# Power.net
KiCad netlist of a schematic drawn in Altium Designer
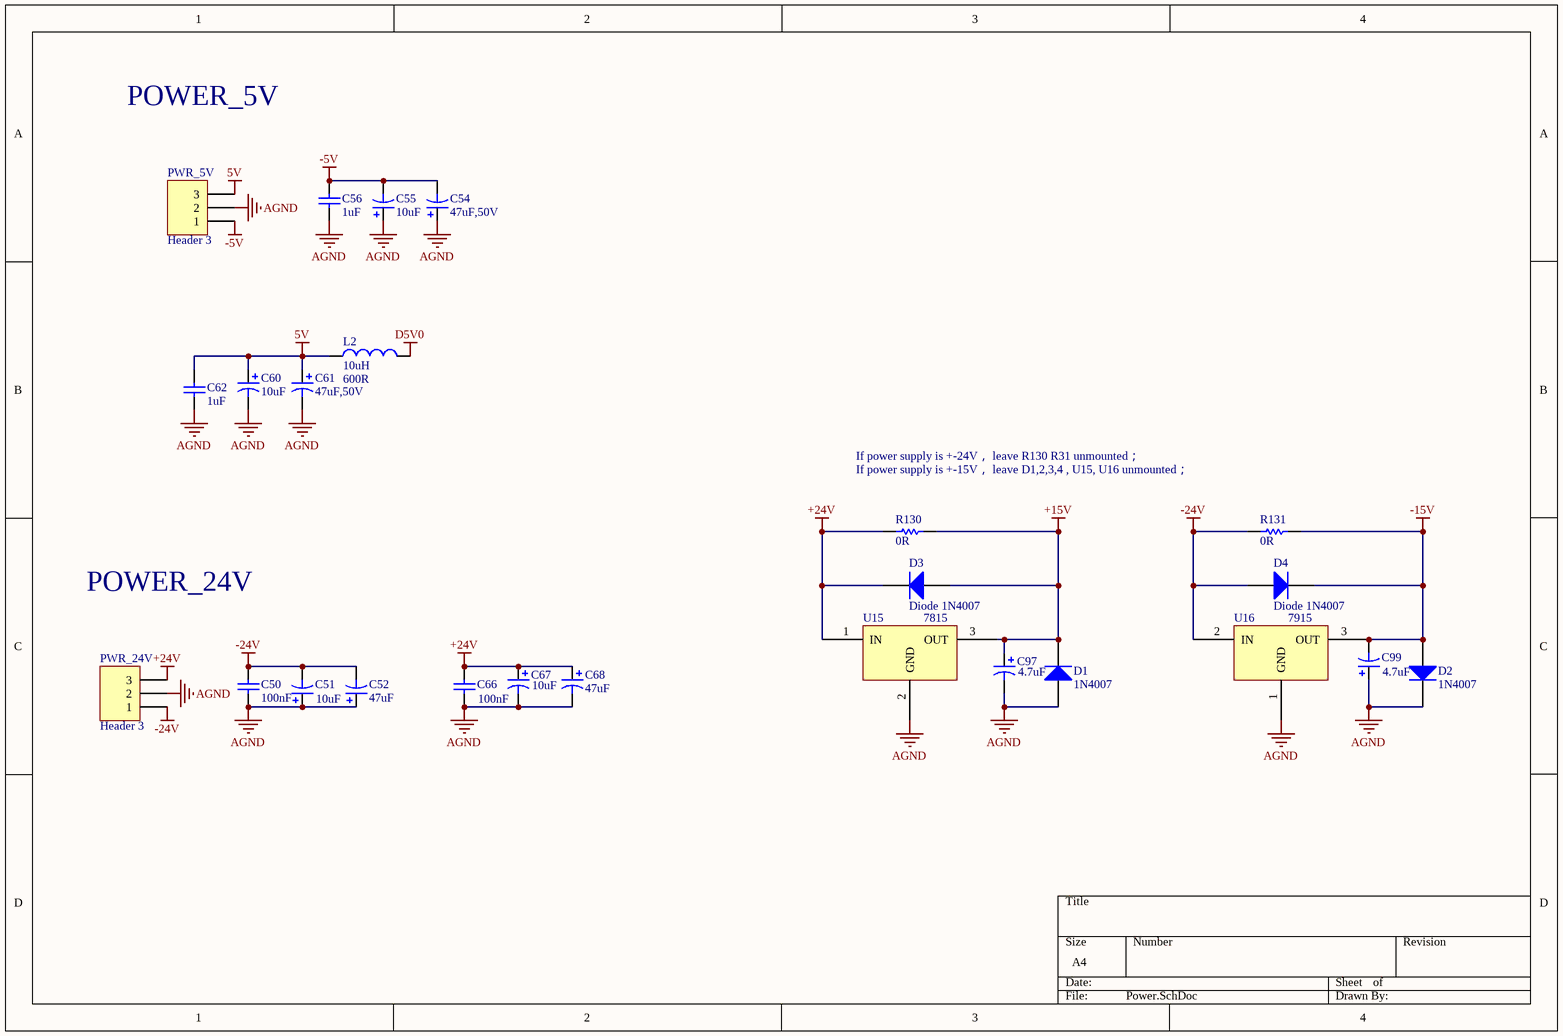
[diagram p0: Power.SchDoc]

(export (version "E")
  (design (tool "Eeschema 10.0.6"))
  (components
    (comp (ref "C50")
      (value "100nF")
      (footprint "0805")
      (description "Capacitor")
      (fields (field (name "PUBLISHER") "Altium Limited"))
      (libsource (lib "Miscellaneous Devices") (part "Cap"))
    )
    (comp (ref "C51")
      (value "10uF")
      (footprint "6032_pol")
      (description "Polarized Capacitor (Radial)")
      (fields (field (name "PUBLISHER") "Altium Limited"))
      (libsource (lib "Miscellaneous Devices") (part "Cap Pol1"))
    )
    (comp (ref "C52")
      (value "47uF")
      (footprint "cap_pol_8*10.2")
      (description "Polarized Capacitor (Radial)")
      (fields (field (name "PUBLISHER") "Altium Limited"))
      (libsource (lib "Miscellaneous Devices") (part "Cap Pol1"))
    )
    (comp (ref "C54")
      (value "47uF,50V")
      (footprint "cap_pol_8*10.2")
      (description "Polarized Capacitor (Radial)")
      (fields (field (name "PUBLISHER") "Altium Limited"))
      (libsource (lib "Miscellaneous Devices") (part "Cap Pol1"))
    )
    (comp (ref "C55")
      (value "10uF")
      (footprint "6032_pol")
      (description "Polarized Capacitor (Radial)")
      (fields (field (name "PUBLISHER") "Altium Limited"))
      (libsource (lib "Miscellaneous Devices") (part "Cap Pol1"))
    )
    (comp (ref "C56")
      (value "1uF")
      (footprint "0805")
      (description "Capacitor,100V")
      (fields (field (name "PUBLISHER") "Altium Limited"))
      (libsource (lib "Miscellaneous Devices") (part "Cap"))
    )
    (comp (ref "C60")
      (value "10uF")
      (footprint "6032_pol")
      (description "Polarized Capacitor (Radial)")
      (fields (field (name "PUBLISHER") "Altium Limited"))
      (libsource (lib "Miscellaneous Devices") (part "Cap Pol1"))
    )
    (comp (ref "C61")
      (value "47uF,50V")
      (footprint "cap_pol_8*10.2")
      (description "Polarized Capacitor (Radial)")
      (fields (field (name "PUBLISHER") "Altium Limited"))
      (libsource (lib "Miscellaneous Devices") (part "Cap Pol1"))
    )
    (comp (ref "C62")
      (value "1uF")
      (footprint "0805")
      (description "Capacitor,100V")
      (fields (field (name "PUBLISHER") "Altium Limited"))
      (libsource (lib "Miscellaneous Devices") (part "Cap"))
    )
    (comp (ref "C66")
      (value "100nF")
      (footprint "0805")
      (description "Capacitor")
      (fields (field (name "PUBLISHER") "Altium Limited"))
      (libsource (lib "Miscellaneous Devices") (part "Cap"))
    )
    (comp (ref "C67")
      (value "10uF")
      (footprint "6032_pol")
      (description "Polarized Capacitor (Radial)")
      (fields (field (name "PUBLISHER") "Altium Limited"))
      (libsource (lib "Miscellaneous Devices") (part "Cap Pol1"))
    )
    (comp (ref "C68")
      (value "47uF")
      (footprint "cap_pol_8*10.2")
      (description "Polarized Capacitor (Radial)")
      (fields (field (name "PUBLISHER") "Altium Limited"))
      (libsource (lib "Miscellaneous Devices") (part "Cap Pol1"))
    )
    (comp (ref "C97")
      (value "4.7uF")
      (footprint "6032_pol")
      (description "Polarized Capacitor (Radial)")
      (fields (field (name "PUBLISHER") "Altium Limited"))
      (libsource (lib "Miscellaneous Devices") (part "Cap Pol1"))
    )
    (comp (ref "C99")
      (value "4.7uF")
      (footprint "6032_pol")
      (description "Polarized Capacitor (Radial)")
      (fields (field (name "PUBLISHER") "Altium Limited"))
      (libsource (lib "Miscellaneous Devices") (part "Cap Pol1"))
    )
    (comp (ref "D1")
      (value "1N4007")
      (footprint "1N4007_M7")
      (description "1 Amp General Purpose Rectifier")
      (fields (field (name "PUBLISHER") "Altium Limited"))
      (libsource (lib "Miscellaneous Devices") (part "Diode 1N4007"))
    )
    (comp (ref "D2")
      (value "1N4007")
      (footprint "1N4007_M7")
      (description "1 Amp General Purpose Rectifier")
      (fields (field (name "PUBLISHER") "Altium Limited"))
      (libsource (lib "Miscellaneous Devices") (part "Diode 1N4007"))
    )
    (comp (ref "D3")
      (value "Diode 1N4007")
      (footprint "1N4007_M7")
      (description "1 Amp General Purpose Rectifier")
      (fields (field (name "PUBLISHER") "Altium Limited"))
      (libsource (lib "Miscellaneous Devices") (part "Diode 1N4007"))
    )
    (comp (ref "D4")
      (value "Diode 1N4007")
      (footprint "1N4007_M7")
      (description "1 Amp General Purpose Rectifier")
      (fields (field (name "PUBLISHER") "Altium Limited"))
      (libsource (lib "Miscellaneous Devices") (part "Diode 1N4007"))
    )
    (comp (ref "L2")
      (value "10uH")
      (footprint "8040")
      (description "Inductor")
      (fields (field (name "ALTIUM_VALUE") "600R") (field (name "PUBLISHER") "Altium Limited"))
      (libsource (lib "Miscellaneous Devices") (part "Inductor"))
    )
    (comp (ref "PWR_5V")
      (value "Header 3")
      (footprint "PWR_3T")
      (description "Header, 3-Pin")
      (fields (field (name "PUBLISHER") "Altium Limited"))
      (libsource (lib "Miscellaneous Connectors") (part "Header 3"))
    )
    (comp (ref "PWR_24V")
      (value "Header 3")
      (footprint "PWR_3T")
      (description "Header, 3-Pin")
      (fields (field (name "PUBLISHER") "Altium Limited"))
      (libsource (lib "Miscellaneous Connectors") (part "Header 3"))
    )
    (comp (ref "R130")
      (value "0R")
      (footprint "1206")
      (description "Resistor")
      (fields (field (name "PUBLISHER") "Altium Limited"))
      (libsource (lib "Miscellaneous Devices") (part "Res1"))
    )
    (comp (ref "R131")
      (value "0R")
      (footprint "1206")
      (description "Resistor")
      (fields (field (name "PUBLISHER") "Altium Limited"))
      (libsource (lib "Miscellaneous Devices") (part "Res1"))
    )
    (comp (ref "U15") (value "7815") (footprint "TO-220") (libsource (lib "BinFeng_IC") (part "7815")))
    (comp (ref "U16") (value "7915") (footprint "TO-220") (libsource (lib "BinFeng_IC") (part "7915")))
  )
  (nets
    (net (code "1") (name "+15V") (class "Default")
      (node (ref "C97") (pin "1") (pinfunction "1_1") (pintype "passive"))
      (node (ref "D1") (pin "2") (pinfunction "K_2") (pintype "passive"))
      (node (ref "D3") (pin "1") (pinfunction "A_1") (pintype "passive"))
      (node (ref "R130") (pin "2") (pinfunction "2_2") (pintype "passive"))
      (node (ref "U15") (pin "3") (pinfunction "OUT_3") (pintype "passive"))
    )
    (net (code "2") (name "+24V") (class "Default")
      (node (ref "C66") (pin "1") (pinfunction "1_1") (pintype "passive"))
      (node (ref "C67") (pin "1") (pinfunction "1_1") (pintype "passive"))
      (node (ref "C68") (pin "1") (pinfunction "1_1") (pintype "passive"))
      (node (ref "D3") (pin "2") (pinfunction "K_2") (pintype "passive"))
      (node (ref "PWR_24V") (pin "3") (pinfunction "3_3") (pintype "passive"))
      (node (ref "R130") (pin "1") (pinfunction "1_1") (pintype "passive"))
      (node (ref "U15") (pin "1") (pinfunction "IN_1") (pintype "passive"))
    )
    (net (code "3") (name "-5V") (class "Default")
      (node (ref "C54") (pin "2") (pinfunction "2_2") (pintype "passive"))
      (node (ref "C55") (pin "2") (pinfunction "2_2") (pintype "passive"))
      (node (ref "C56") (pin "2") (pinfunction "2_2") (pintype "passive"))
      (node (ref "PWR_5V") (pin "1") (pinfunction "1_1") (pintype "passive"))
    )
    (net (code "4") (name "-15V") (class "Default")
      (node (ref "C99") (pin "2") (pinfunction "2_2") (pintype "passive"))
      (node (ref "D2") (pin "1") (pinfunction "A_1") (pintype "passive"))
      (node (ref "D4") (pin "2") (pinfunction "K_2") (pintype "passive"))
      (node (ref "R131") (pin "2") (pinfunction "2_2") (pintype "passive"))
      (node (ref "U16") (pin "3") (pinfunction "OUT_3") (pintype "passive"))
    )
    (net (code "5") (name "-24V") (class "Default")
      (node (ref "C50") (pin "1") (pinfunction "1_1") (pintype "passive"))
      (node (ref "C51") (pin "2") (pinfunction "2_2") (pintype "passive"))
      (node (ref "C52") (pin "2") (pinfunction "2_2") (pintype "passive"))
      (node (ref "D4") (pin "1") (pinfunction "A_1") (pintype "passive"))
      (node (ref "PWR_24V") (pin "1") (pinfunction "1_1") (pintype "passive"))
      (node (ref "R131") (pin "1") (pinfunction "1_1") (pintype "passive"))
      (node (ref "U16") (pin "2") (pinfunction "IN_2") (pintype "passive"))
    )
    (net (code "6") (name "5V") (class "Default")
      (node (ref "C60") (pin "1") (pinfunction "1_1") (pintype "passive"))
      (node (ref "C61") (pin "1") (pinfunction "1_1") (pintype "passive"))
      (node (ref "C62") (pin "2") (pinfunction "2_2") (pintype "passive"))
      (node (ref "L2") (pin "1") (pinfunction "1_1") (pintype "passive"))
      (node (ref "PWR_5V") (pin "3") (pinfunction "3_3") (pintype "passive"))
    )
    (net (code "7") (name "AGND") (class "Default")
      (node (ref "C50") (pin "2") (pinfunction "2_2") (pintype "passive"))
      (node (ref "C51") (pin "1") (pinfunction "1_1") (pintype "passive"))
      (node (ref "C52") (pin "1") (pinfunction "1_1") (pintype "passive"))
      (node (ref "C54") (pin "1") (pinfunction "1_1") (pintype "passive"))
      (node (ref "C55") (pin "1") (pinfunction "1_1") (pintype "passive"))
      (node (ref "C56") (pin "1") (pinfunction "1_1") (pintype "passive"))
      (node (ref "C60") (pin "2") (pinfunction "2_2") (pintype "passive"))
      (node (ref "C61") (pin "2") (pinfunction "2_2") (pintype "passive"))
      (node (ref "C62") (pin "1") (pinfunction "1_1") (pintype "passive"))
      (node (ref "C66") (pin "2") (pinfunction "2_2") (pintype "passive"))
      (node (ref "C67") (pin "2") (pinfunction "2_2") (pintype "passive"))
      (node (ref "C68") (pin "2") (pinfunction "2_2") (pintype "passive"))
      (node (ref "C97") (pin "2") (pinfunction "2_2") (pintype "passive"))
      (node (ref "C99") (pin "1") (pinfunction "1_1") (pintype "passive"))
      (node (ref "D1") (pin "1") (pinfunction "A_1") (pintype "passive"))
      (node (ref "D2") (pin "2") (pinfunction "K_2") (pintype "passive"))
      (node (ref "PWR_24V") (pin "2") (pinfunction "2_2") (pintype "passive"))
      (node (ref "PWR_5V") (pin "2") (pinfunction "2_2") (pintype "passive"))
      (node (ref "U15") (pin "2") (pinfunction "GND_2") (pintype "passive"))
      (node (ref "U16") (pin "1") (pinfunction "GND_1") (pintype "passive"))
    )
    (net (code "8") (name "D5V0") (class "Default")
      (node (ref "L2") (pin "2") (pinfunction "2_2") (pintype "passive"))
    )
  )
)
